# ioboard.net
KiCad netlist of a schematic drawn in EAGLE
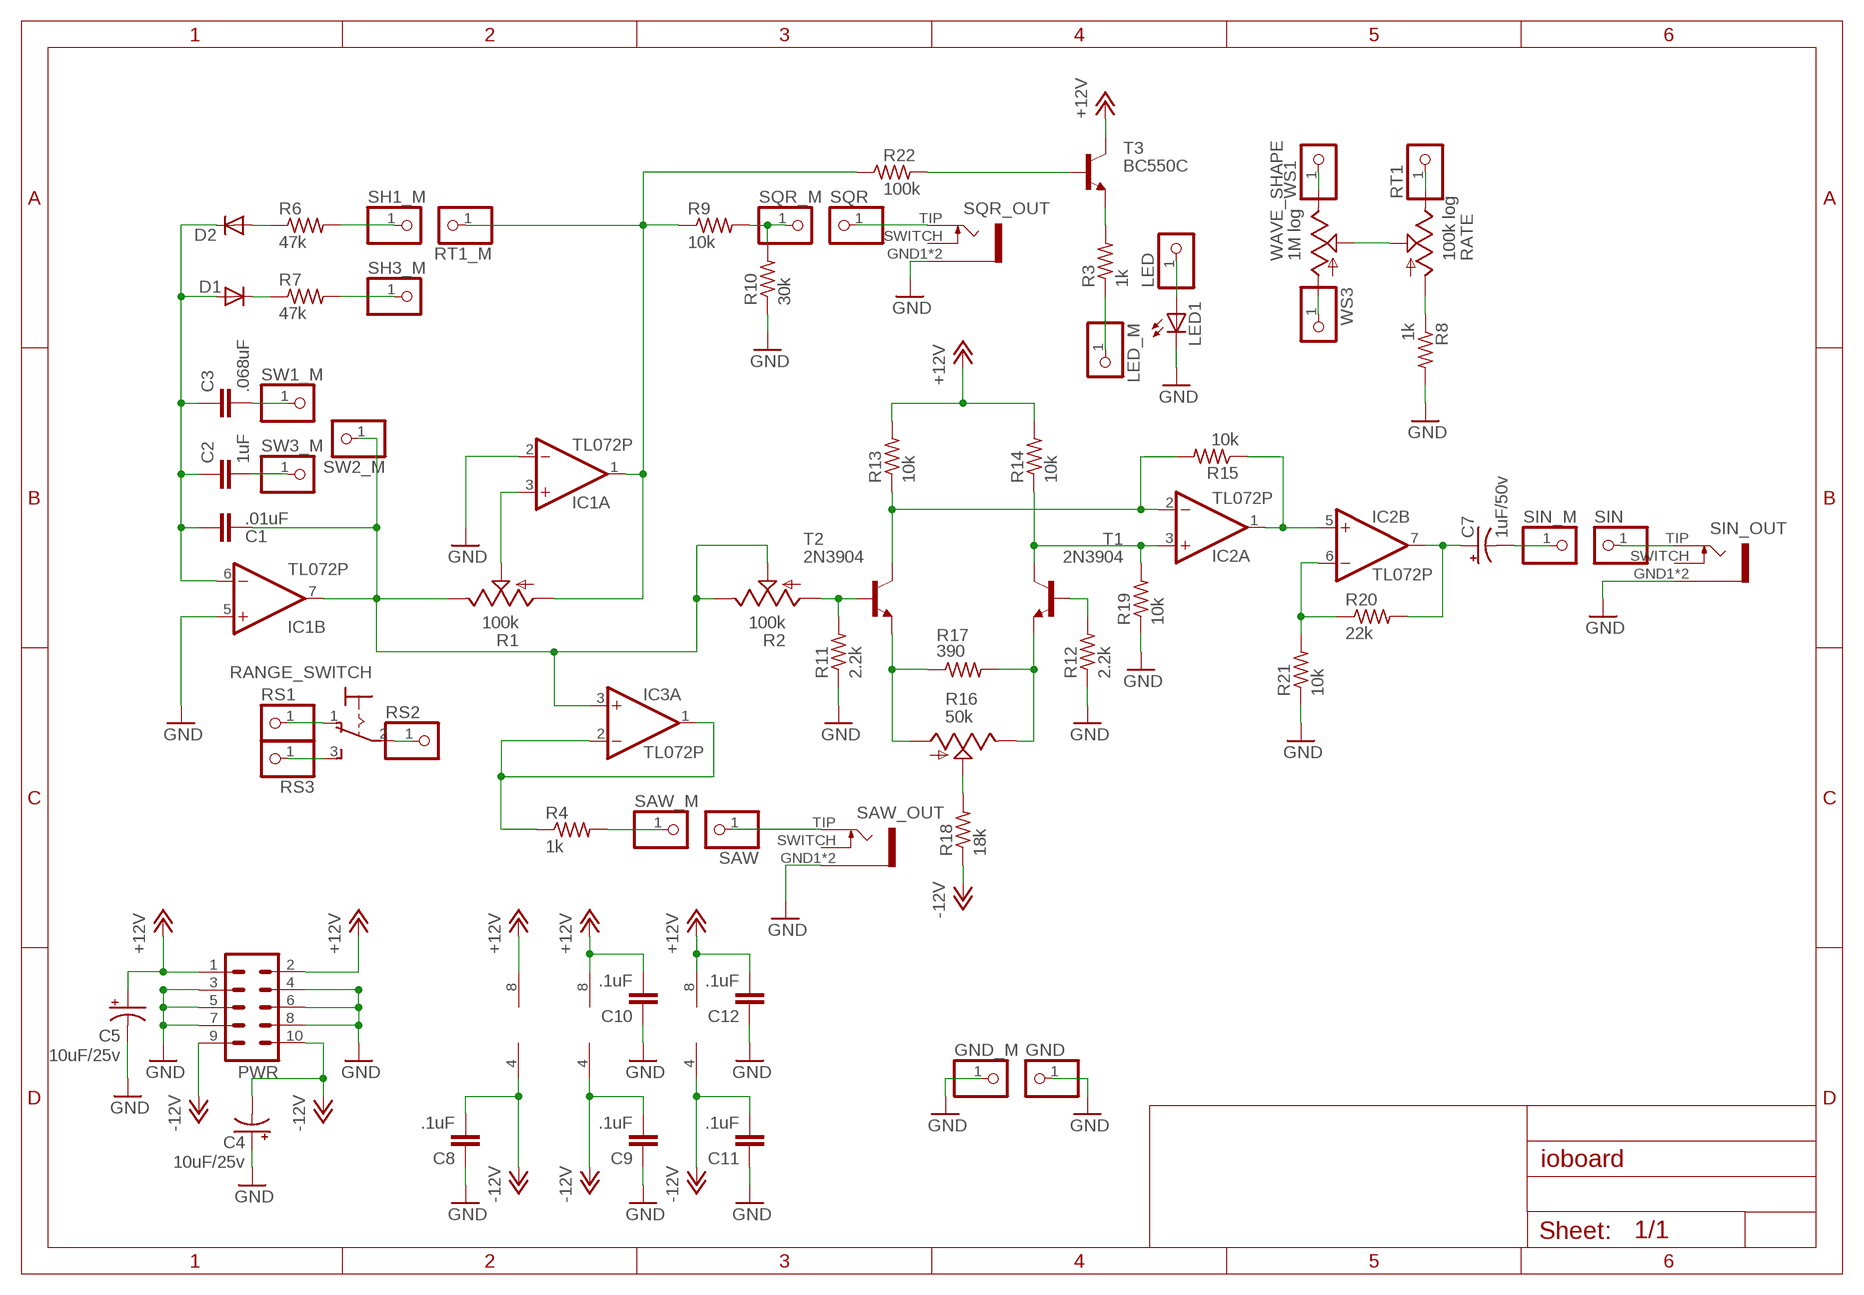
[diagram p0: schematic, sheet 1]

(export (version "E")
  (design (tool "Eeschema 10.0.6"))
  (components
    (comp (ref "C1")
      (value ".01uF")
      (footprint "eagle-import:C050-025X075")
      (libsource (lib "eagle-import") (part "C-EU050-025X075"))
    )
    (comp (ref "C2")
      (value "1uF")
      (footprint "eagle-import:C050-025X075")
      (libsource (lib "eagle-import") (part "C-EU050-025X075"))
    )
    (comp (ref "C3")
      (value ".068uF")
      (footprint "eagle-import:C050-025X075")
      (libsource (lib "eagle-import") (part "C-EU050-025X075"))
    )
    (comp (ref "C4")
      (value "10uF/25v")
      (footprint "eagle-import:E2,5-5")
      (libsource (lib "eagle-import") (part "CPOL-USE2.5-5"))
    )
    (comp (ref "C5")
      (value "10uF/25v")
      (footprint "eagle-import:E2,5-5")
      (libsource (lib "eagle-import") (part "CPOL-USE2.5-5"))
    )
    (comp (ref "C7")
      (value "1uF/50v")
      (footprint "eagle-import:E2,5-5")
      (libsource (lib "eagle-import") (part "CPOL-USE2.5-5"))
    )
    (comp (ref "C8")
      (value ".1uF")
      (footprint "eagle-import:C025-024X044")
      (libsource (lib "eagle-import") (part "C-EU025-024X044"))
    )
    (comp (ref "C9")
      (value ".1uF")
      (footprint "eagle-import:C025-024X044")
      (libsource (lib "eagle-import") (part "C-EU025-024X044"))
    )
    (comp (ref "C10")
      (value ".1uF")
      (footprint "eagle-import:C025-024X044")
      (libsource (lib "eagle-import") (part "C-EU025-024X044"))
    )
    (comp (ref "C11")
      (value ".1uF")
      (footprint "eagle-import:C025-024X044")
      (libsource (lib "eagle-import") (part "C-EU025-024X044"))
    )
    (comp (ref "C12")
      (value ".1uF")
      (footprint "eagle-import:C025-024X044")
      (libsource (lib "eagle-import") (part "C-EU025-024X044"))
    )
    (comp (ref "D1")
      (value "1N4148DO35-7")
      (footprint "eagle-import:DO35-7")
      (libsource (lib "eagle-import") (part "1N4148DO35-7"))
    )
    (comp (ref "D2")
      (value "1N4148DO35-7")
      (footprint "eagle-import:DO35-7")
      (libsource (lib "eagle-import") (part "1N4148DO35-7"))
    )
    (comp (ref "GND")
      (value "PINHD-1X1")
      (footprint "eagle-import:1X01")
      (libsource (lib "eagle-import") (part "PINHD-1X1"))
    )
    (comp (ref "GND_M")
      (value "PINHD-1X1")
      (footprint "eagle-import:1X01")
      (libsource (lib "eagle-import") (part "PINHD-1X1"))
    )
    (comp (ref "IC1")
      (value "TL072P")
      (footprint "eagle-import:DIL08")
      (libsource (lib "eagle-import") (part "TL072P"))
    )
    (comp (ref "IC2")
      (value "TL072P")
      (footprint "eagle-import:DIL08")
      (libsource (lib "eagle-import") (part "TL072P"))
    )
    (comp (ref "IC3")
      (value "TL072P")
      (footprint "eagle-import:DIL08")
      (libsource (lib "eagle-import") (part "TL072P"))
    )
    (comp (ref "LED")
      (value "PINHD-1X1")
      (footprint "eagle-import:1X01")
      (libsource (lib "eagle-import") (part "PINHD-1X1"))
    )
    (comp (ref "LED1")
      (value "LED5MM")
      (footprint "eagle-import:LED5MM")
      (libsource (lib "eagle-import") (part "LED5MM"))
    )
    (comp (ref "LED_M")
      (value "PINHD-1X1")
      (footprint "eagle-import:1X01")
      (libsource (lib "eagle-import") (part "PINHD-1X1"))
    )
    (comp (ref "PWR")
      (value "ML10")
      (footprint "eagle-import:ML10")
      (libsource (lib "eagle-import") (part "ML10"))
    )
    (comp (ref "R1")
      (value "100k")
      (footprint "eagle-import:RJ9W")
      (libsource (lib "eagle-import") (part "TRIM_US-RJ9W"))
    )
    (comp (ref "R2")
      (value "100k")
      (footprint "eagle-import:RJ9W")
      (libsource (lib "eagle-import") (part "TRIM_US-RJ9W"))
    )
    (comp (ref "R3")
      (value "1k")
      (footprint "eagle-import:0207_10")
      (libsource (lib "eagle-import") (part "R-US_0207/10"))
    )
    (comp (ref "R4")
      (value "1k")
      (footprint "eagle-import:0207_2V")
      (libsource (lib "eagle-import") (part "R-US_0207/2V"))
    )
    (comp (ref "R6")
      (value "47k")
      (footprint "eagle-import:0207_10")
      (libsource (lib "eagle-import") (part "R-US_0207/10"))
    )
    (comp (ref "R7")
      (value "47k")
      (footprint "eagle-import:0207_10")
      (libsource (lib "eagle-import") (part "R-US_0207/10"))
    )
    (comp (ref "R8")
      (value "1k")
      (footprint "eagle-import:0207_10")
      (libsource (lib "eagle-import") (part "R-US_0207/10"))
    )
    (comp (ref "R9")
      (value "10k")
      (footprint "eagle-import:0207_10")
      (libsource (lib "eagle-import") (part "R-US_0207/10"))
    )
    (comp (ref "R10")
      (value "30k")
      (footprint "eagle-import:0207_10")
      (libsource (lib "eagle-import") (part "R-US_0207/10"))
    )
    (comp (ref "R11")
      (value "2.2k")
      (footprint "eagle-import:0207_10")
      (libsource (lib "eagle-import") (part "R-US_0207/10"))
    )
    (comp (ref "R12")
      (value "2.2k")
      (footprint "eagle-import:0207_10")
      (libsource (lib "eagle-import") (part "R-US_0207/10"))
    )
    (comp (ref "R13")
      (value "10k")
      (footprint "eagle-import:0207_10")
      (libsource (lib "eagle-import") (part "R-US_0207/10"))
    )
    (comp (ref "R14")
      (value "10k")
      (footprint "eagle-import:0207_2V")
      (libsource (lib "eagle-import") (part "R-US_0207/2V"))
    )
    (comp (ref "R15")
      (value "10k")
      (footprint "eagle-import:0207_2V")
      (libsource (lib "eagle-import") (part "R-US_0207/2V"))
    )
    (comp (ref "R16")
      (value "50k")
      (footprint "eagle-import:RJ9W")
      (libsource (lib "eagle-import") (part "TRIM_US-RJ9W"))
    )
    (comp (ref "R17")
      (value "390")
      (footprint "eagle-import:0207_10")
      (libsource (lib "eagle-import") (part "R-US_0207/10"))
    )
    (comp (ref "R18")
      (value "18k")
      (footprint "eagle-import:0207_10")
      (libsource (lib "eagle-import") (part "R-US_0207/10"))
    )
    (comp (ref "R19")
      (value "10k")
      (footprint "eagle-import:0207_2V")
      (libsource (lib "eagle-import") (part "R-US_0207/2V"))
    )
    (comp (ref "R20")
      (value "22k")
      (footprint "eagle-import:0207_2V")
      (libsource (lib "eagle-import") (part "R-US_0207/2V"))
    )
    (comp (ref "R21")
      (value "10k")
      (footprint "eagle-import:0207_2V")
      (libsource (lib "eagle-import") (part "R-US_0207/2V"))
    )
    (comp (ref "R22")
      (value "100k")
      (footprint "eagle-import:0207_10")
      (libsource (lib "eagle-import") (part "R-US_0207/10"))
    )
    (comp (ref "RANGE_SWITCH")
      (value "M9040P")
      (footprint "eagle-import:M9040P")
      (libsource (lib "eagle-import") (part "M9040P"))
    )
    (comp (ref "RATE")
      (value "100k log")
      (footprint "eagle-import:EVUF")
      (libsource (lib "eagle-import") (part "ALPHA-9MMA"))
    )
    (comp (ref "RS1")
      (value "PINHD-1X1")
      (footprint "eagle-import:1X01")
      (libsource (lib "eagle-import") (part "PINHD-1X1"))
    )
    (comp (ref "RS2")
      (value "PINHD-1X1")
      (footprint "eagle-import:1X01")
      (libsource (lib "eagle-import") (part "PINHD-1X1"))
    )
    (comp (ref "RS3")
      (value "PINHD-1X1")
      (footprint "eagle-import:1X01")
      (libsource (lib "eagle-import") (part "PINHD-1X1"))
    )
    (comp (ref "RT1")
      (value "PINHD-1X1")
      (footprint "eagle-import:1X01")
      (libsource (lib "eagle-import") (part "PINHD-1X1"))
    )
    (comp (ref "RT1_M")
      (value "PINHD-1X1")
      (footprint "eagle-import:1X01")
      (libsource (lib "eagle-import") (part "PINHD-1X1"))
    )
    (comp (ref "SAW")
      (value "PINHD-1X1")
      (footprint "eagle-import:1X01")
      (libsource (lib "eagle-import") (part "PINHD-1X1"))
    )
    (comp (ref "SAW_M")
      (value "PINHD-1X1")
      (footprint "eagle-import:1X01")
      (libsource (lib "eagle-import") (part "PINHD-1X1"))
    )
    (comp (ref "SAW_OUT")
      (value "PJ301BMPJ301BM")
      (footprint "eagle-import:PJ301BM")
      (libsource (lib "eagle-import") (part "PJ301BMPJ301BM"))
    )
    (comp (ref "SH1_M")
      (value "PINHD-1X1")
      (footprint "eagle-import:1X01")
      (libsource (lib "eagle-import") (part "PINHD-1X1"))
    )
    (comp (ref "SH3_M")
      (value "PINHD-1X1")
      (footprint "eagle-import:1X01")
      (libsource (lib "eagle-import") (part "PINHD-1X1"))
    )
    (comp (ref "SIN")
      (value "PINHD-1X1")
      (footprint "eagle-import:1X01")
      (libsource (lib "eagle-import") (part "PINHD-1X1"))
    )
    (comp (ref "SIN_M")
      (value "PINHD-1X1")
      (footprint "eagle-import:1X01")
      (libsource (lib "eagle-import") (part "PINHD-1X1"))
    )
    (comp (ref "SIN_OUT")
      (value "PJ301BMPJ301BM")
      (footprint "eagle-import:PJ301BM")
      (libsource (lib "eagle-import") (part "PJ301BMPJ301BM"))
    )
    (comp (ref "SQR")
      (value "PINHD-1X1")
      (footprint "eagle-import:1X01")
      (libsource (lib "eagle-import") (part "PINHD-1X1"))
    )
    (comp (ref "SQR_M")
      (value "PINHD-1X1")
      (footprint "eagle-import:1X01")
      (libsource (lib "eagle-import") (part "PINHD-1X1"))
    )
    (comp (ref "SQR_OUT")
      (value "PJ301BMPJ301BM")
      (footprint "eagle-import:PJ301BM")
      (libsource (lib "eagle-import") (part "PJ301BMPJ301BM"))
    )
    (comp (ref "SW1_M")
      (value "PINHD-1X1")
      (footprint "eagle-import:1X01")
      (libsource (lib "eagle-import") (part "PINHD-1X1"))
    )
    (comp (ref "SW2_M")
      (value "PINHD-1X1")
      (footprint "eagle-import:1X01")
      (libsource (lib "eagle-import") (part "PINHD-1X1"))
    )
    (comp (ref "SW3_M")
      (value "PINHD-1X1")
      (footprint "eagle-import:1X01")
      (libsource (lib "eagle-import") (part "PINHD-1X1"))
    )
    (comp (ref "T1")
      (value "2N3904")
      (footprint "eagle-import:TO92")
      (libsource (lib "eagle-import") (part "2N3904"))
    )
    (comp (ref "T2")
      (value "2N3904")
      (footprint "eagle-import:TO92")
      (libsource (lib "eagle-import") (part "2N3904"))
    )
    (comp (ref "T3")
      (value "BC550C")
      (footprint "eagle-import:TO92-CBE")
      (libsource (lib "eagle-import") (part "-NPN-TO92-CBEBC550"))
    )
    (comp (ref "WAVE_SHAPE")
      (value "1M log")
      (footprint "eagle-import:EVUF")
      (libsource (lib "eagle-import") (part "ALPHA-9MMA"))
    )
    (comp (ref "WS1")
      (value "PINHD-1X1")
      (footprint "eagle-import:1X01")
      (libsource (lib "eagle-import") (part "PINHD-1X1"))
    )
    (comp (ref "WS3")
      (value "PINHD-1X1")
      (footprint "eagle-import:1X01")
      (libsource (lib "eagle-import") (part "PINHD-1X1"))
    )
  )
  (nets
    (net (code "1") (name "+12V") (class "Default")
      (node (ref "C10") (pin "2") (pinfunction "2_2") (pintype "passive"))
      (node (ref "C12") (pin "2") (pinfunction "2_2") (pintype "passive"))
      (node (ref "C5") (pin "+") (pinfunction "+_+") (pintype "passive"))
      (node (ref "IC1") (pin "8") (pinfunction "V+_8") (pintype "power_in"))
      (node (ref "IC2") (pin "8") (pinfunction "V+_8") (pintype "power_in"))
      (node (ref "IC3") (pin "8") (pinfunction "V+_8") (pintype "power_in"))
      (node (ref "PWR") (pin "1") (pinfunction "1_1") (pintype "passive"))
      (node (ref "PWR") (pin "2") (pinfunction "2_2") (pintype "passive"))
      (node (ref "R13") (pin "2") (pinfunction "2_2") (pintype "passive"))
      (node (ref "R14") (pin "2") (pinfunction "2_2") (pintype "passive"))
      (node (ref "T3") (pin "C") (pinfunction "C_C") (pintype "passive"))
    )
    (net (code "2") (name "-12V") (class "Default")
      (node (ref "C11") (pin "2") (pinfunction "2_2") (pintype "passive"))
      (node (ref "C4") (pin "-") (pinfunction "-_-") (pintype "passive"))
      (node (ref "C8") (pin "2") (pinfunction "2_2") (pintype "passive"))
      (node (ref "C9") (pin "2") (pinfunction "2_2") (pintype "passive"))
      (node (ref "IC1") (pin "4") (pinfunction "V-_4") (pintype "power_in"))
      (node (ref "IC2") (pin "4") (pinfunction "V-_4") (pintype "power_in"))
      (node (ref "IC3") (pin "4") (pinfunction "V-_4") (pintype "power_in"))
      (node (ref "PWR") (pin "10") (pinfunction "10_10") (pintype "passive"))
      (node (ref "PWR") (pin "9") (pinfunction "9_9") (pintype "passive"))
      (node (ref "R18") (pin "1") (pinfunction "1_1") (pintype "passive"))
    )
    (net (code "3") (name "GND") (class "Default")
      (node (ref "C10") (pin "1") (pinfunction "1_1") (pintype "passive"))
      (node (ref "C11") (pin "1") (pinfunction "1_1") (pintype "passive"))
      (node (ref "C12") (pin "1") (pinfunction "1_1") (pintype "passive"))
      (node (ref "C4") (pin "+") (pinfunction "+_+") (pintype "passive"))
      (node (ref "C5") (pin "-") (pinfunction "-_-") (pintype "passive"))
      (node (ref "C8") (pin "1") (pinfunction "1_1") (pintype "passive"))
      (node (ref "C9") (pin "1") (pinfunction "1_1") (pintype "passive"))
      (node (ref "GND") (pin "1") (pinfunction "1_1") (pintype "passive"))
      (node (ref "GND_M") (pin "1") (pinfunction "1_1") (pintype "passive"))
      (node (ref "IC1") (pin "2") (pinfunction "-IN_2") (pintype "input"))
      (node (ref "IC1") (pin "5") (pinfunction "+IN_5") (pintype "input"))
      (node (ref "LED1") (pin "K") (pinfunction "C_K") (pintype "passive"))
      (node (ref "PWR") (pin "3") (pinfunction "3_3") (pintype "passive"))
      (node (ref "PWR") (pin "4") (pinfunction "4_4") (pintype "passive"))
      (node (ref "PWR") (pin "5") (pinfunction "5_5") (pintype "passive"))
      (node (ref "PWR") (pin "6") (pinfunction "6_6") (pintype "passive"))
      (node (ref "PWR") (pin "7") (pinfunction "7_7") (pintype "passive"))
      (node (ref "PWR") (pin "8") (pinfunction "8_8") (pintype "passive"))
      (node (ref "R10") (pin "1") (pinfunction "1_1") (pintype "passive"))
      (node (ref "R11") (pin "1") (pinfunction "1_1") (pintype "passive"))
      (node (ref "R12") (pin "1") (pinfunction "1_1") (pintype "passive"))
      (node (ref "R19") (pin "1") (pinfunction "1_1") (pintype "passive"))
      (node (ref "R21") (pin "1") (pinfunction "1_1") (pintype "passive"))
      (node (ref "R8") (pin "2") (pinfunction "2_2") (pintype "passive"))
      (node (ref "SAW_OUT") (pin "GND1") (pinfunction "5_GND1") (pintype "passive"))
      (node (ref "SAW_OUT") (pin "GND2") (pinfunction "5_GND2") (pintype "passive"))
      (node (ref "SIN_OUT") (pin "GND1") (pinfunction "5_GND1") (pintype "passive"))
      (node (ref "SIN_OUT") (pin "GND2") (pinfunction "5_GND2") (pintype "passive"))
      (node (ref "SQR_OUT") (pin "GND1") (pinfunction "5_GND1") (pintype "passive"))
      (node (ref "SQR_OUT") (pin "GND2") (pinfunction "5_GND2") (pintype "passive"))
    )
    (net (code "4") (name "Net-(C2-Pad2)") (class "Default")
      (node (ref "C2") (pin "2") (pinfunction "2_2") (pintype "passive"))
      (node (ref "SW3_M") (pin "1") (pinfunction "1_1") (pintype "passive"))
    )
    (net (code "5") (name "Net-(C3-Pad2)") (class "Default")
      (node (ref "C3") (pin "2") (pinfunction "2_2") (pintype "passive"))
      (node (ref "SW1_M") (pin "1") (pinfunction "1_1") (pintype "passive"))
    )
    (net (code "6") (name "Net-(C7-Pad-)") (class "Default")
      (node (ref "C7") (pin "-") (pinfunction "-_-") (pintype "passive"))
      (node (ref "SIN_M") (pin "1") (pinfunction "1_1") (pintype "passive"))
    )
    (net (code "7") (name "Net-(D1-PadC)") (class "Default")
      (node (ref "D1") (pin "C") (pinfunction "C_C") (pintype "passive"))
      (node (ref "R7") (pin "1") (pinfunction "1_1") (pintype "passive"))
    )
    (net (code "8") (name "Net-(D2-PadA)") (class "Default")
      (node (ref "D2") (pin "A") (pinfunction "A_A") (pintype "passive"))
      (node (ref "R6") (pin "1") (pinfunction "1_1") (pintype "passive"))
    )
    (net (code "9") (name "Net-(IC1A-+IN)") (class "Default")
      (node (ref "IC1") (pin "3") (pinfunction "+IN_3") (pintype "input"))
      (node (ref "R1") (pin "S") (pinfunction "S_S") (pintype "passive"))
    )
    (net (code "10") (name "Net-(IC1A-OUT)") (class "Default")
      (node (ref "IC1") (pin "1") (pinfunction "OUT_1") (pintype "output"))
      (node (ref "R1") (pin "A") (pinfunction "A_A") (pintype "passive"))
      (node (ref "R22") (pin "1") (pinfunction "1_1") (pintype "passive"))
      (node (ref "R9") (pin "1") (pinfunction "1_1") (pintype "passive"))
      (node (ref "RT1_M") (pin "1") (pinfunction "1_1") (pintype "passive"))
    )
    (net (code "11") (name "Net-(IC1B--IN)") (class "Default")
      (node (ref "C1") (pin "1") (pinfunction "1_1") (pintype "passive"))
      (node (ref "C2") (pin "1") (pinfunction "1_1") (pintype "passive"))
      (node (ref "C3") (pin "1") (pinfunction "1_1") (pintype "passive"))
      (node (ref "D1") (pin "A") (pinfunction "A_A") (pintype "passive"))
      (node (ref "D2") (pin "C") (pinfunction "C_C") (pintype "passive"))
      (node (ref "IC1") (pin "6") (pinfunction "-IN_6") (pintype "input"))
    )
    (net (code "12") (name "Net-(IC1B-OUT)") (class "Default")
      (node (ref "C1") (pin "2") (pinfunction "2_2") (pintype "passive"))
      (node (ref "IC1") (pin "7") (pinfunction "OUT_7") (pintype "output"))
      (node (ref "IC3") (pin "3") (pinfunction "+IN_3") (pintype "input"))
      (node (ref "R1") (pin "E") (pinfunction "E_E") (pintype "passive"))
      (node (ref "R2") (pin "E") (pinfunction "E_E") (pintype "passive"))
      (node (ref "R2") (pin "S") (pinfunction "S_S") (pintype "passive"))
      (node (ref "SW2_M") (pin "1") (pinfunction "1_1") (pintype "passive"))
    )
    (net (code "13") (name "Net-(IC2A-+IN)") (class "Default")
      (node (ref "IC2") (pin "3") (pinfunction "+IN_3") (pintype "input"))
      (node (ref "R14") (pin "1") (pinfunction "1_1") (pintype "passive"))
      (node (ref "R19") (pin "2") (pinfunction "2_2") (pintype "passive"))
      (node (ref "T1") (pin "1") (pinfunction "C_1") (pintype "passive"))
    )
    (net (code "14") (name "Net-(IC2A--IN)") (class "Default")
      (node (ref "IC2") (pin "2") (pinfunction "-IN_2") (pintype "input"))
      (node (ref "R13") (pin "1") (pinfunction "1_1") (pintype "passive"))
      (node (ref "R15") (pin "2") (pinfunction "2_2") (pintype "passive"))
      (node (ref "T2") (pin "1") (pinfunction "C_1") (pintype "passive"))
    )
    (net (code "15") (name "Net-(IC2A-OUT)") (class "Default")
      (node (ref "IC2") (pin "1") (pinfunction "OUT_1") (pintype "output"))
      (node (ref "IC2") (pin "5") (pinfunction "+IN_5") (pintype "input"))
      (node (ref "R15") (pin "1") (pinfunction "1_1") (pintype "passive"))
    )
    (net (code "16") (name "Net-(IC2B--IN)") (class "Default")
      (node (ref "IC2") (pin "6") (pinfunction "-IN_6") (pintype "input"))
      (node (ref "R20") (pin "1") (pinfunction "1_1") (pintype "passive"))
      (node (ref "R21") (pin "2") (pinfunction "2_2") (pintype "passive"))
    )
    (net (code "17") (name "Net-(IC2B-OUT)") (class "Default")
      (node (ref "C7") (pin "+") (pinfunction "+_+") (pintype "passive"))
      (node (ref "IC2") (pin "7") (pinfunction "OUT_7") (pintype "output"))
      (node (ref "R20") (pin "2") (pinfunction "2_2") (pintype "passive"))
    )
    (net (code "18") (name "Net-(IC3A--IN)") (class "Default")
      (node (ref "IC3") (pin "1") (pinfunction "OUT_1") (pintype "output"))
      (node (ref "IC3") (pin "2") (pinfunction "-IN_2") (pintype "input"))
      (node (ref "R4") (pin "1") (pinfunction "1_1") (pintype "passive"))
    )
    (net (code "19") (name "Net-(LED-Pad1)") (class "Default")
      (node (ref "LED") (pin "1") (pinfunction "1_1") (pintype "passive"))
      (node (ref "LED1") (pin "A") (pinfunction "A_A") (pintype "passive"))
    )
    (net (code "20") (name "Net-(LED_M-Pad1)") (class "Default")
      (node (ref "LED_M") (pin "1") (pinfunction "1_1") (pintype "passive"))
      (node (ref "R3") (pin "1") (pinfunction "1_1") (pintype "passive"))
    )
    (net (code "21") (name "Net-(R3-Pad2)") (class "Default")
      (node (ref "R3") (pin "2") (pinfunction "2_2") (pintype "passive"))
      (node (ref "T3") (pin "E") (pinfunction "E_E") (pintype "passive"))
    )
    (net (code "22") (name "Net-(R4-Pad2)") (class "Default")
      (node (ref "R4") (pin "2") (pinfunction "2_2") (pintype "passive"))
      (node (ref "SAW_M") (pin "1") (pinfunction "1_1") (pintype "passive"))
    )
    (net (code "23") (name "Net-(R6-Pad2)") (class "Default")
      (node (ref "R6") (pin "2") (pinfunction "2_2") (pintype "passive"))
      (node (ref "SH1_M") (pin "1") (pinfunction "1_1") (pintype "passive"))
    )
    (net (code "24") (name "Net-(R7-Pad2)") (class "Default")
      (node (ref "R7") (pin "2") (pinfunction "2_2") (pintype "passive"))
      (node (ref "SH3_M") (pin "1") (pinfunction "1_1") (pintype "passive"))
    )
    (net (code "25") (name "Net-(R10-Pad2)") (class "Default")
      (node (ref "R10") (pin "2") (pinfunction "2_2") (pintype "passive"))
      (node (ref "R9") (pin "2") (pinfunction "2_2") (pintype "passive"))
      (node (ref "SQR_M") (pin "1") (pinfunction "1_1") (pintype "passive"))
    )
    (net (code "26") (name "Net-(R16-PadS)") (class "Default")
      (node (ref "R16") (pin "S") (pinfunction "S_S") (pintype "passive"))
      (node (ref "R18") (pin "2") (pinfunction "2_2") (pintype "passive"))
    )
    (net (code "27") (name "Net-(R22-Pad2)") (class "Default")
      (node (ref "R22") (pin "2") (pinfunction "2_2") (pintype "passive"))
      (node (ref "T3") (pin "B") (pinfunction "B_B") (pintype "passive"))
    )
    (net (code "28") (name "Net-(RANGE_SWITCH-O)") (class "Default")
      (node (ref "RANGE_SWITCH") (pin "1") (pinfunction "O_1") (pintype "passive"))
      (node (ref "RS1") (pin "1") (pinfunction "1_1") (pintype "passive"))
    )
    (net (code "29") (name "Net-(RANGE_SWITCH-P)") (class "Default")
      (node (ref "RANGE_SWITCH") (pin "2") (pinfunction "P_2") (pintype "passive"))
      (node (ref "RS2") (pin "1") (pinfunction "1_1") (pintype "passive"))
    )
    (net (code "30") (name "Net-(RANGE_SWITCH-S)") (class "Default")
      (node (ref "RANGE_SWITCH") (pin "3") (pinfunction "S_3") (pintype "passive"))
      (node (ref "RS3") (pin "1") (pinfunction "1_1") (pintype "passive"))
    )
    (net (code "31") (name "Net-(RATE-A)") (class "Default")
      (node (ref "R8") (pin "1") (pinfunction "1_1") (pintype "passive"))
      (node (ref "RATE") (pin "1") (pinfunction "A_1") (pintype "passive"))
    )
    (net (code "32") (name "Net-(RATE-E)") (class "Default")
      (node (ref "RATE") (pin "3") (pinfunction "E_3") (pintype "passive"))
      (node (ref "RT1") (pin "1") (pinfunction "1_1") (pintype "passive"))
    )
    (net (code "33") (name "Net-(RATE-S)") (class "Default")
      (node (ref "RATE") (pin "2") (pinfunction "S_2") (pintype "passive"))
      (node (ref "WAVE_SHAPE") (pin "2") (pinfunction "S_2") (pintype "passive"))
    )
    (net (code "34") (name "Net-(SAW_OUT-3)") (class "Default")
      (node (ref "SAW") (pin "1") (pinfunction "1_1") (pintype "passive"))
      (node (ref "SAW_OUT") (pin "TIP") (pinfunction "3_TIP") (pintype "passive"))
    )
    (net (code "35") (name "Net-(SIN_OUT-3)") (class "Default")
      (node (ref "SIN") (pin "1") (pinfunction "1_1") (pintype "passive"))
      (node (ref "SIN_OUT") (pin "TIP") (pinfunction "3_TIP") (pintype "passive"))
    )
    (net (code "36") (name "Net-(SQR_OUT-3)") (class "Default")
      (node (ref "SQR") (pin "1") (pinfunction "1_1") (pintype "passive"))
      (node (ref "SQR_OUT") (pin "TIP") (pinfunction "3_TIP") (pintype "passive"))
    )
    (net (code "37") (name "Net-(T1-B)") (class "Default")
      (node (ref "R12") (pin "2") (pinfunction "2_2") (pintype "passive"))
      (node (ref "T1") (pin "2") (pinfunction "B_2") (pintype "passive"))
    )
    (net (code "38") (name "Net-(T1-E)") (class "Default")
      (node (ref "R16") (pin "E") (pinfunction "E_E") (pintype "passive"))
      (node (ref "R17") (pin "2") (pinfunction "2_2") (pintype "passive"))
      (node (ref "T1") (pin "3") (pinfunction "E_3") (pintype "passive"))
    )
    (net (code "39") (name "Net-(T2-B)") (class "Default")
      (node (ref "R11") (pin "2") (pinfunction "2_2") (pintype "passive"))
      (node (ref "R2") (pin "A") (pinfunction "A_A") (pintype "passive"))
      (node (ref "T2") (pin "2") (pinfunction "B_2") (pintype "passive"))
    )
    (net (code "40") (name "Net-(T2-E)") (class "Default")
      (node (ref "R16") (pin "A") (pinfunction "A_A") (pintype "passive"))
      (node (ref "R17") (pin "1") (pinfunction "1_1") (pintype "passive"))
      (node (ref "T2") (pin "3") (pinfunction "E_3") (pintype "passive"))
    )
    (net (code "41") (name "Net-(WAVE_SHAPE-A)") (class "Default")
      (node (ref "WAVE_SHAPE") (pin "1") (pinfunction "A_1") (pintype "passive"))
      (node (ref "WS3") (pin "1") (pinfunction "1_1") (pintype "passive"))
    )
    (net (code "42") (name "Net-(WAVE_SHAPE-E)") (class "Default")
      (node (ref "WAVE_SHAPE") (pin "3") (pinfunction "E_3") (pintype "passive"))
      (node (ref "WS1") (pin "1") (pinfunction "1_1") (pintype "passive"))
    )
    (net (code "43") (name "unconnected-(SAW_OUT-4-PadSWITCH)") (class "Default")
      (node (ref "SAW_OUT") (pin "SWITCH") (pinfunction "4_SWITCH") (pintype "passive"))
    )
    (net (code "44") (name "unconnected-(SIN_OUT-4-PadSWITCH)") (class "Default")
      (node (ref "SIN_OUT") (pin "SWITCH") (pinfunction "4_SWITCH") (pintype "passive"))
    )
    (net (code "45") (name "unconnected-(SQR_OUT-4-PadSWITCH)") (class "Default")
      (node (ref "SQR_OUT") (pin "SWITCH") (pinfunction "4_SWITCH") (pintype "passive"))
    )
  )
)
